# basic-schematic.net
KiCad netlist of a schematic drawn in EAGLE
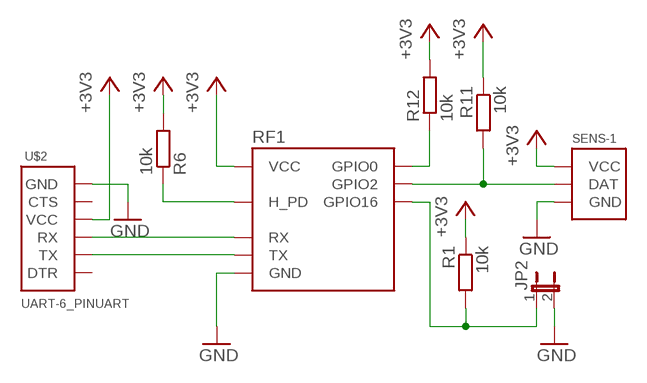
[diagram p0: schematic, sheet 1]

(export (version "E")
  (design (tool "Eeschema 10.0.6"))
  (components
    (comp (ref "JP2")
      (value "JP1E")
      (footprint "eagle-import:JP1")
      (libsource (lib "eagle-import") (part "JP1E"))
    )
    (comp (ref "R1")
      (value "10k")
      (footprint "eagle-import:0207_7")
      (libsource (lib "eagle-import") (part "R-EU_0207/7"))
    )
    (comp (ref "R6")
      (value "10k")
      (footprint "eagle-import:0207_7")
      (libsource (lib "eagle-import") (part "R-EU_0207/7"))
    )
    (comp (ref "R11")
      (value "10k")
      (footprint "eagle-import:0207_7")
      (libsource (lib "eagle-import") (part "R-EU_0207/7"))
    )
    (comp (ref "R12")
      (value "10k")
      (footprint "eagle-import:0207_7")
      (libsource (lib "eagle-import") (part "R-EU_0207/7"))
    )
    (comp (ref "RF1")
      (value "ESP2866-ESP-01THT")
      (footprint "eagle-import:ESP8266-ESP-01")
      (libsource (lib "eagle-import") (part "ESP2866-ESP-01THT"))
    )
    (comp (ref "SENS-1")
      (value "DHT11DHT11")
      (footprint "eagle-import:SENSOR-DHT11")
      (libsource (lib "eagle-import") (part "DHT11DHT11"))
    )
    (comp (ref "U$2")
      (value "UART-6_PINUART")
      (footprint "eagle-import:ANGLE-1X6")
      (libsource (lib "eagle-import") (part "UART-6_PINUART"))
    )
  )
  (nets
    (net (code "1") (name "+3V3") (class "Default")
      (node (ref "R1") (pin "1") (pinfunction "1_1") (pintype "passive"))
      (node (ref "R11") (pin "1") (pinfunction "1_1") (pintype "passive"))
      (node (ref "R12") (pin "2") (pinfunction "2_2") (pintype "passive"))
      (node (ref "R6") (pin "2") (pinfunction "2_2") (pintype "passive"))
      (node (ref "RF1") (pin "VCC") (pinfunction "VCC_VCC") (pintype "bidirectional"))
      (node (ref "SENS-1") (pin "P$1") (pinfunction "VCC_P$1") (pintype "bidirectional"))
      (node (ref "U$2") (pin "3") (pinfunction "VCC_3") (pintype "bidirectional"))
    )
    (net (code "2") (name "GND") (class "Default")
      (node (ref "JP2") (pin "2") (pinfunction "2_2") (pintype "passive"))
      (node (ref "RF1") (pin "GND") (pinfunction "GND_GND") (pintype "bidirectional"))
      (node (ref "SENS-1") (pin "P$4") (pinfunction "GND_P$4") (pintype "bidirectional"))
      (node (ref "U$2") (pin "1") (pinfunction "GND_1") (pintype "bidirectional"))
    )
    (net (code "3") (name "Net-(JP2-Pad1)") (class "Default")
      (node (ref "JP2") (pin "1") (pinfunction "1_1") (pintype "passive"))
      (node (ref "R1") (pin "2") (pinfunction "2_2") (pintype "passive"))
      (node (ref "RF1") (pin "GPIO16") (pinfunction "GPIO16_GPIO16") (pintype "bidirectional"))
    )
    (net (code "4") (name "Net-(R6-Pad1)") (class "Default")
      (node (ref "R6") (pin "1") (pinfunction "1_1") (pintype "passive"))
      (node (ref "RF1") (pin "H_PD") (pinfunction "H_PD_H_PD") (pintype "bidirectional"))
    )
    (net (code "5") (name "Net-(R12-Pad1)") (class "Default")
      (node (ref "R12") (pin "1") (pinfunction "1_1") (pintype "passive"))
      (node (ref "RF1") (pin "GPIO0") (pinfunction "GPIO0_GPIO0") (pintype "bidirectional"))
    )
    (net (code "6") (name "Net-(SENS-1-DAT)") (class "Default")
      (node (ref "R11") (pin "2") (pinfunction "2_2") (pintype "passive"))
      (node (ref "RF1") (pin "GPIO2") (pinfunction "GPIO2_GPIO2") (pintype "bidirectional"))
      (node (ref "SENS-1") (pin "P$2") (pinfunction "DAT_P$2") (pintype "bidirectional"))
    )
    (net (code "7") (name "Net-(U$2-RX)") (class "Default")
      (node (ref "RF1") (pin "RX") (pinfunction "RX_RX") (pintype "bidirectional"))
      (node (ref "U$2") (pin "4") (pinfunction "RX_4") (pintype "bidirectional"))
    )
    (net (code "8") (name "Net-(U$2-TX)") (class "Default")
      (node (ref "RF1") (pin "TX") (pinfunction "TX_TX") (pintype "bidirectional"))
      (node (ref "U$2") (pin "5") (pinfunction "TX_5") (pintype "bidirectional"))
    )
    (net (code "9") (name "unconnected-(U$2-CTS-Pad2)") (class "Default")
      (node (ref "U$2") (pin "2") (pinfunction "CTS_2") (pintype "bidirectional"))
    )
    (net (code "10") (name "unconnected-(U$2-DTR-Pad6)") (class "Default")
      (node (ref "U$2") (pin "6") (pinfunction "DTR_6") (pintype "bidirectional"))
    )
  )
)
